# driverMotor.net
KiCad netlist of a schematic drawn in EAGLE
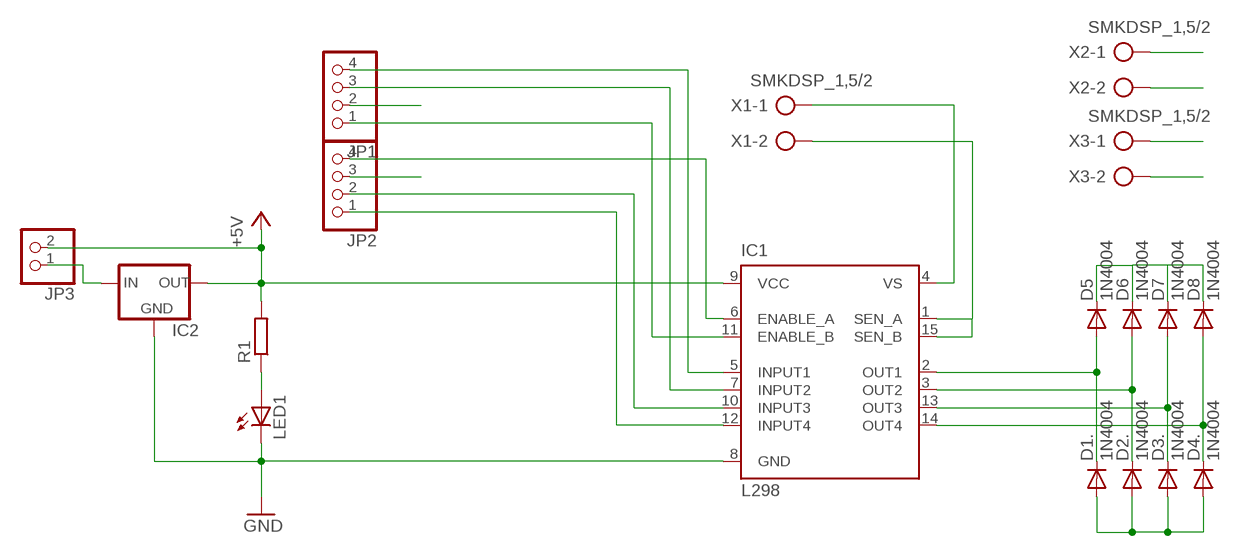
[diagram p0: schematic, sheet 1]

(export (version "E")
  (design (tool "Eeschema 10.0.6"))
  (components
    (comp (ref "D1.")
      (value "1N4004")
      (footprint "eagle-import:DO41-10")
      (libsource (lib "eagle-import") (part "1N4004"))
    )
    (comp (ref "D2.")
      (value "1N4004")
      (footprint "eagle-import:DO41-10")
      (libsource (lib "eagle-import") (part "1N4004"))
    )
    (comp (ref "D3.")
      (value "1N4004")
      (footprint "eagle-import:DO41-10")
      (libsource (lib "eagle-import") (part "1N4004"))
    )
    (comp (ref "D4.")
      (value "1N4004")
      (footprint "eagle-import:DO41-10")
      (libsource (lib "eagle-import") (part "1N4004"))
    )
    (comp (ref "D5")
      (value "1N4004")
      (footprint "eagle-import:DO41-10")
      (libsource (lib "eagle-import") (part "1N4004"))
    )
    (comp (ref "D6")
      (value "1N4004")
      (footprint "eagle-import:DO41-10")
      (libsource (lib "eagle-import") (part "1N4004"))
    )
    (comp (ref "D7")
      (value "1N4004")
      (footprint "eagle-import:DO41-10")
      (libsource (lib "eagle-import") (part "1N4004"))
    )
    (comp (ref "D8")
      (value "1N4004")
      (footprint "eagle-import:DO41-10")
      (libsource (lib "eagle-import") (part "1N4004"))
    )
    (comp (ref "IC1")
      (value "L298")
      (footprint "eagle-import:MULTIWATT-15")
      (libsource (lib "eagle-import") (part "L298"))
    )
    (comp (ref "IC2")
      (value "78MXXS")
      (footprint "eagle-import:78MXXS")
      (libsource (lib "eagle-import") (part "78MXXS"))
    )
    (comp (ref "JP1")
      (value "PINHD-1X4")
      (footprint "eagle-import:1X04")
      (libsource (lib "eagle-import") (part "PINHD-1X4"))
    )
    (comp (ref "JP2")
      (value "PINHD-1X4")
      (footprint "eagle-import:1X04")
      (libsource (lib "eagle-import") (part "PINHD-1X4"))
    )
    (comp (ref "JP3")
      (value "PINHD-1X2")
      (footprint "eagle-import:1X02")
      (libsource (lib "eagle-import") (part "PINHD-1X2"))
    )
    (comp (ref "LED1")
      (value "LED5MM")
      (footprint "eagle-import:LED5MM")
      (libsource (lib "eagle-import") (part "LED5MM"))
    )
    (comp (ref "R1")
      (value "R-EU_0411/12")
      (footprint "eagle-import:0411_12")
      (libsource (lib "eagle-import") (part "R-EU_0411/12"))
    )
    (comp (ref "X1")
      (value "SMKDSP_1,5/2")
      (footprint "eagle-import:SMKDSP_1,5_2")
      (fields (field (name "MF") "FARNELL") (field (name "MPN") "1733570"))
      (libsource (lib "eagle-import") (part "SMKDSP_1,5/2"))
    )
    (comp (ref "X2")
      (value "SMKDSP_1,5/2")
      (footprint "eagle-import:SMKDSP_1,5_2")
      (fields (field (name "MF") "FARNELL") (field (name "MPN") "1733570"))
      (libsource (lib "eagle-import") (part "SMKDSP_1,5/2"))
    )
    (comp (ref "X3")
      (value "SMKDSP_1,5/2")
      (footprint "eagle-import:SMKDSP_1,5_2")
      (fields (field (name "MF") "FARNELL") (field (name "MPN") "1733570"))
      (libsource (lib "eagle-import") (part "SMKDSP_1,5/2"))
    )
  )
  (nets
    (net (code "1") (name "+5V") (class "Default")
      (node (ref "IC1") (pin "9") (pinfunction "VCC_9") (pintype "power_in"))
      (node (ref "IC2") (pin "OUT") (pinfunction "OUT_OUT") (pintype "passive"))
      (node (ref "JP1") (pin "2") (pinfunction "2_2") (pintype "passive"))
      (node (ref "JP3") (pin "2") (pinfunction "2_2") (pintype "passive"))
      (node (ref "R1") (pin "2") (pinfunction "2_2") (pintype "passive"))
    )
    (net (code "2") (name "/MOTOR1_1") (class "Default")
      (node (ref "D1.") (pin "C") (pinfunction "C_C") (pintype "passive"))
      (node (ref "D5") (pin "A") (pinfunction "A_A") (pintype "passive"))
      (node (ref "IC1") (pin "2") (pinfunction "OUT1_2") (pintype "output"))
      (node (ref "X2") (pin "1") (pinfunction "KL_1") (pintype "passive"))
    )
    (net (code "3") (name "/MOTOR1_2") (class "Default")
      (node (ref "D2.") (pin "C") (pinfunction "C_C") (pintype "passive"))
      (node (ref "D6") (pin "A") (pinfunction "A_A") (pintype "passive"))
      (node (ref "IC1") (pin "3") (pinfunction "OUT2_3") (pintype "output"))
      (node (ref "X2") (pin "2") (pinfunction "KL_2") (pintype "passive"))
    )
    (net (code "4") (name "/MOTOR2_1") (class "Default")
      (node (ref "D3.") (pin "C") (pinfunction "C_C") (pintype "passive"))
      (node (ref "D7") (pin "A") (pinfunction "A_A") (pintype "passive"))
      (node (ref "IC1") (pin "13") (pinfunction "OUT3_13") (pintype "output"))
      (node (ref "X3") (pin "1") (pinfunction "KL_1") (pintype "passive"))
    )
    (net (code "5") (name "/MOTOR2_2") (class "Default")
      (node (ref "D4.") (pin "C") (pinfunction "C_C") (pintype "passive"))
      (node (ref "D8") (pin "A") (pinfunction "A_A") (pintype "passive"))
      (node (ref "IC1") (pin "14") (pinfunction "OUT4_14") (pintype "output"))
      (node (ref "X3") (pin "2") (pinfunction "KL_2") (pintype "passive"))
    )
    (net (code "6") (name "/VS") (class "Default")
      (node (ref "D5") (pin "C") (pinfunction "C_C") (pintype "passive"))
      (node (ref "D6") (pin "C") (pinfunction "C_C") (pintype "passive"))
      (node (ref "D7") (pin "C") (pinfunction "C_C") (pintype "passive"))
      (node (ref "D8") (pin "C") (pinfunction "C_C") (pintype "passive"))
      (node (ref "IC1") (pin "4") (pinfunction "VS_4") (pintype "power_in"))
      (node (ref "X1") (pin "1") (pinfunction "KL_1") (pintype "passive"))
    )
    (net (code "7") (name "GND") (class "Default")
      (node (ref "D1.") (pin "A") (pinfunction "A_A") (pintype "passive"))
      (node (ref "D2.") (pin "A") (pinfunction "A_A") (pintype "passive"))
      (node (ref "D3.") (pin "A") (pinfunction "A_A") (pintype "passive"))
      (node (ref "D4.") (pin "A") (pinfunction "A_A") (pintype "passive"))
      (node (ref "IC1") (pin "1") (pinfunction "SEN_A_1") (pintype "input"))
      (node (ref "IC1") (pin "15") (pinfunction "SEN_B_15") (pintype "input"))
      (node (ref "IC1") (pin "8") (pinfunction "GND_8") (pintype "power_in"))
      (node (ref "IC2") (pin "GND") (pinfunction "GND_GND") (pintype "input"))
      (node (ref "JP2") (pin "3") (pinfunction "3_3") (pintype "passive"))
      (node (ref "LED1") (pin "K") (pinfunction "C_K") (pintype "passive"))
      (node (ref "X1") (pin "2") (pinfunction "KL_2") (pintype "passive"))
    )
    (net (code "8") (name "Net-(IC1-ENABLE_A)") (class "Default")
      (node (ref "IC1") (pin "6") (pinfunction "ENABLE_A_6") (pintype "input"))
      (node (ref "JP2") (pin "4") (pinfunction "4_4") (pintype "passive"))
    )
    (net (code "9") (name "Net-(IC1-ENABLE_B)") (class "Default")
      (node (ref "IC1") (pin "11") (pinfunction "ENABLE_B_11") (pintype "input"))
      (node (ref "JP1") (pin "1") (pinfunction "1_1") (pintype "passive"))
    )
    (net (code "10") (name "Net-(IC1-INPUT1)") (class "Default")
      (node (ref "IC1") (pin "5") (pinfunction "INPUT1_5") (pintype "input"))
      (node (ref "JP1") (pin "4") (pinfunction "4_4") (pintype "passive"))
    )
    (net (code "11") (name "Net-(IC1-INPUT2)") (class "Default")
      (node (ref "IC1") (pin "7") (pinfunction "INPUT2_7") (pintype "input"))
      (node (ref "JP1") (pin "3") (pinfunction "3_3") (pintype "passive"))
    )
    (net (code "12") (name "Net-(IC1-INPUT3)") (class "Default")
      (node (ref "IC1") (pin "10") (pinfunction "INPUT3_10") (pintype "input"))
      (node (ref "JP2") (pin "2") (pinfunction "2_2") (pintype "passive"))
    )
    (net (code "13") (name "Net-(IC1-INPUT4)") (class "Default")
      (node (ref "IC1") (pin "12") (pinfunction "INPUT4_12") (pintype "input"))
      (node (ref "JP2") (pin "1") (pinfunction "1_1") (pintype "passive"))
    )
    (net (code "14") (name "Net-(IC2-PadIN)") (class "Default")
      (node (ref "IC2") (pin "IN") (pinfunction "IN_IN") (pintype "input"))
      (node (ref "JP3") (pin "1") (pinfunction "1_1") (pintype "passive"))
    )
    (net (code "15") (name "Net-(LED1-PadA)") (class "Default")
      (node (ref "LED1") (pin "A") (pinfunction "A_A") (pintype "passive"))
      (node (ref "R1") (pin "1") (pinfunction "1_1") (pintype "passive"))
    )
  )
)
